# main.net
KiCad netlist of a schematic drawn in EAGLE
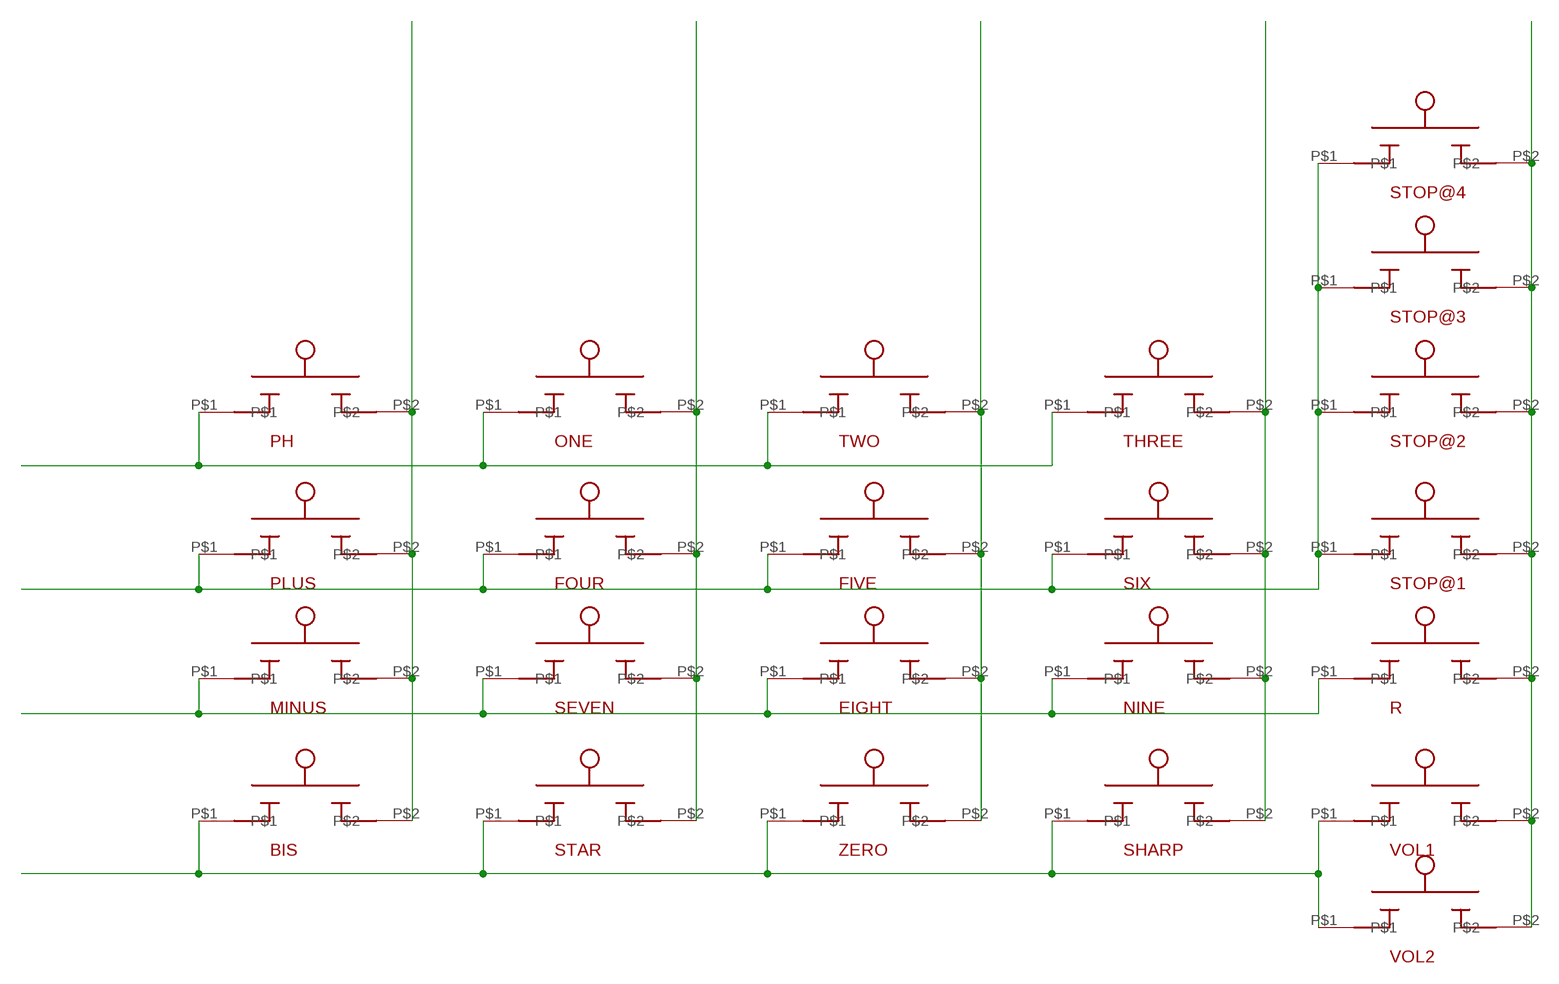
[diagram p0: schematic, sheet 1]

(export (version "E")
  (design (tool "Eeschema 10.0.6"))
  (components
    (comp (ref "BIS")
      (value "MEMBRANE_BUTTON")
      (footprint "eagle-import:MEMBRANE_BUTTON")
      (libsource (lib "eagle-import") (part "MEMBRANE_BUTTON"))
    )
    (comp (ref "EIGHT")
      (value "MEMBRANE_BUTTON")
      (footprint "eagle-import:MEMBRANE_BUTTON")
      (libsource (lib "eagle-import") (part "MEMBRANE_BUTTON"))
    )
    (comp (ref "FIVE")
      (value "MEMBRANE_BUTTON")
      (footprint "eagle-import:MEMBRANE_BUTTON")
      (libsource (lib "eagle-import") (part "MEMBRANE_BUTTON"))
    )
    (comp (ref "FOUR")
      (value "MEMBRANE_BUTTON")
      (footprint "eagle-import:MEMBRANE_BUTTON")
      (libsource (lib "eagle-import") (part "MEMBRANE_BUTTON"))
    )
    (comp (ref "MINUS")
      (value "MEMBRANE_BUTTON")
      (footprint "eagle-import:MEMBRANE_BUTTON")
      (libsource (lib "eagle-import") (part "MEMBRANE_BUTTON"))
    )
    (comp (ref "NINE")
      (value "MEMBRANE_BUTTON")
      (footprint "eagle-import:MEMBRANE_BUTTON")
      (libsource (lib "eagle-import") (part "MEMBRANE_BUTTON"))
    )
    (comp (ref "ONE")
      (value "MEMBRANE_BUTTON")
      (footprint "eagle-import:MEMBRANE_BUTTON")
      (libsource (lib "eagle-import") (part "MEMBRANE_BUTTON"))
    )
    (comp (ref "PH")
      (value "MEMBRANE_BUTTON")
      (footprint "eagle-import:MEMBRANE_BUTTON")
      (libsource (lib "eagle-import") (part "MEMBRANE_BUTTON"))
    )
    (comp (ref "PLUS")
      (value "MEMBRANE_BUTTON")
      (footprint "eagle-import:MEMBRANE_BUTTON")
      (libsource (lib "eagle-import") (part "MEMBRANE_BUTTON"))
    )
    (comp (ref "R")
      (value "MEMBRANE_BUTTON")
      (footprint "eagle-import:MEMBRANE_BUTTON")
      (libsource (lib "eagle-import") (part "MEMBRANE_BUTTON"))
    )
    (comp (ref "SEVEN")
      (value "MEMBRANE_BUTTON")
      (footprint "eagle-import:MEMBRANE_BUTTON")
      (libsource (lib "eagle-import") (part "MEMBRANE_BUTTON"))
    )
    (comp (ref "SHARP")
      (value "MEMBRANE_BUTTON")
      (footprint "eagle-import:MEMBRANE_BUTTON")
      (libsource (lib "eagle-import") (part "MEMBRANE_BUTTON"))
    )
    (comp (ref "SIX")
      (value "MEMBRANE_BUTTON")
      (footprint "eagle-import:MEMBRANE_BUTTON")
      (libsource (lib "eagle-import") (part "MEMBRANE_BUTTON"))
    )
    (comp (ref "STAR")
      (value "MEMBRANE_BUTTON")
      (footprint "eagle-import:MEMBRANE_BUTTON")
      (libsource (lib "eagle-import") (part "MEMBRANE_BUTTON"))
    )
    (comp (ref "STOP@1")
      (value "MEMBRANE_BUTTON")
      (footprint "eagle-import:MEMBRANE_BUTTON")
      (libsource (lib "eagle-import") (part "MEMBRANE_BUTTON"))
    )
    (comp (ref "STOP@2")
      (value "MEMBRANE_BUTTON")
      (footprint "eagle-import:MEMBRANE_BUTTON")
      (libsource (lib "eagle-import") (part "MEMBRANE_BUTTON"))
    )
    (comp (ref "STOP@3")
      (value "MEMBRANE_BUTTON")
      (footprint "eagle-import:MEMBRANE_BUTTON")
      (libsource (lib "eagle-import") (part "MEMBRANE_BUTTON"))
    )
    (comp (ref "STOP@4")
      (value "MEMBRANE_BUTTON")
      (footprint "eagle-import:MEMBRANE_BUTTON")
      (libsource (lib "eagle-import") (part "MEMBRANE_BUTTON"))
    )
    (comp (ref "THREE")
      (value "MEMBRANE_BUTTON")
      (footprint "eagle-import:MEMBRANE_BUTTON")
      (libsource (lib "eagle-import") (part "MEMBRANE_BUTTON"))
    )
    (comp (ref "TWO")
      (value "MEMBRANE_BUTTON")
      (footprint "eagle-import:MEMBRANE_BUTTON")
      (libsource (lib "eagle-import") (part "MEMBRANE_BUTTON"))
    )
    (comp (ref "VOL1")
      (value "MEMBRANE_BUTTON")
      (footprint "eagle-import:MEMBRANE_BUTTON")
      (libsource (lib "eagle-import") (part "MEMBRANE_BUTTON"))
    )
    (comp (ref "VOL2")
      (value "MEMBRANE_BUTTON")
      (footprint "eagle-import:MEMBRANE_BUTTON")
      (libsource (lib "eagle-import") (part "MEMBRANE_BUTTON"))
    )
    (comp (ref "ZERO")
      (value "MEMBRANE_BUTTON")
      (footprint "eagle-import:MEMBRANE_BUTTON")
      (libsource (lib "eagle-import") (part "MEMBRANE_BUTTON"))
    )
  )
  (nets
    (net (code "1") (name "Net-(BIS-PadP$1)") (class "Default")
      (node (ref "BIS") (pin "P$1") (pinfunction "P$1_P$1") (pintype "bidirectional"))
      (node (ref "SHARP") (pin "P$1") (pinfunction "P$1_P$1") (pintype "bidirectional"))
      (node (ref "STAR") (pin "P$1") (pinfunction "P$1_P$1") (pintype "bidirectional"))
      (node (ref "VOL1") (pin "P$1") (pinfunction "P$1_P$1") (pintype "bidirectional"))
      (node (ref "VOL2") (pin "P$1") (pinfunction "P$1_P$1") (pintype "bidirectional"))
      (node (ref "ZERO") (pin "P$1") (pinfunction "P$1_P$1") (pintype "bidirectional"))
    )
    (net (code "2") (name "Net-(BIS-PadP$2)") (class "Default")
      (node (ref "BIS") (pin "P$2") (pinfunction "P$2_P$2") (pintype "bidirectional"))
      (node (ref "MINUS") (pin "P$2") (pinfunction "P$2_P$2") (pintype "bidirectional"))
      (node (ref "PH") (pin "P$2") (pinfunction "P$2_P$2") (pintype "bidirectional"))
      (node (ref "PLUS") (pin "P$2") (pinfunction "P$2_P$2") (pintype "bidirectional"))
    )
    (net (code "3") (name "Net-(EIGHT-PadP$1)") (class "Default")
      (node (ref "EIGHT") (pin "P$1") (pinfunction "P$1_P$1") (pintype "bidirectional"))
      (node (ref "MINUS") (pin "P$1") (pinfunction "P$1_P$1") (pintype "bidirectional"))
      (node (ref "NINE") (pin "P$1") (pinfunction "P$1_P$1") (pintype "bidirectional"))
      (node (ref "R") (pin "P$1") (pinfunction "P$1_P$1") (pintype "bidirectional"))
      (node (ref "SEVEN") (pin "P$1") (pinfunction "P$1_P$1") (pintype "bidirectional"))
    )
    (net (code "4") (name "Net-(EIGHT-PadP$2)") (class "Default")
      (node (ref "EIGHT") (pin "P$2") (pinfunction "P$2_P$2") (pintype "bidirectional"))
      (node (ref "FIVE") (pin "P$2") (pinfunction "P$2_P$2") (pintype "bidirectional"))
      (node (ref "TWO") (pin "P$2") (pinfunction "P$2_P$2") (pintype "bidirectional"))
      (node (ref "ZERO") (pin "P$2") (pinfunction "P$2_P$2") (pintype "bidirectional"))
    )
    (net (code "5") (name "Net-(FIVE-PadP$1)") (class "Default")
      (node (ref "FIVE") (pin "P$1") (pinfunction "P$1_P$1") (pintype "bidirectional"))
      (node (ref "FOUR") (pin "P$1") (pinfunction "P$1_P$1") (pintype "bidirectional"))
      (node (ref "PLUS") (pin "P$1") (pinfunction "P$1_P$1") (pintype "bidirectional"))
      (node (ref "SIX") (pin "P$1") (pinfunction "P$1_P$1") (pintype "bidirectional"))
      (node (ref "STOP@1") (pin "P$1") (pinfunction "P$1_P$1") (pintype "bidirectional"))
      (node (ref "STOP@2") (pin "P$1") (pinfunction "P$1_P$1") (pintype "bidirectional"))
      (node (ref "STOP@3") (pin "P$1") (pinfunction "P$1_P$1") (pintype "bidirectional"))
      (node (ref "STOP@4") (pin "P$1") (pinfunction "P$1_P$1") (pintype "bidirectional"))
    )
    (net (code "6") (name "Net-(FOUR-PadP$2)") (class "Default")
      (node (ref "FOUR") (pin "P$2") (pinfunction "P$2_P$2") (pintype "bidirectional"))
      (node (ref "ONE") (pin "P$2") (pinfunction "P$2_P$2") (pintype "bidirectional"))
      (node (ref "SEVEN") (pin "P$2") (pinfunction "P$2_P$2") (pintype "bidirectional"))
      (node (ref "STAR") (pin "P$2") (pinfunction "P$2_P$2") (pintype "bidirectional"))
    )
    (net (code "7") (name "Net-(NINE-PadP$2)") (class "Default")
      (node (ref "NINE") (pin "P$2") (pinfunction "P$2_P$2") (pintype "bidirectional"))
      (node (ref "SHARP") (pin "P$2") (pinfunction "P$2_P$2") (pintype "bidirectional"))
      (node (ref "SIX") (pin "P$2") (pinfunction "P$2_P$2") (pintype "bidirectional"))
      (node (ref "THREE") (pin "P$2") (pinfunction "P$2_P$2") (pintype "bidirectional"))
    )
    (net (code "8") (name "Net-(ONE-PadP$1)") (class "Default")
      (node (ref "ONE") (pin "P$1") (pinfunction "P$1_P$1") (pintype "bidirectional"))
      (node (ref "PH") (pin "P$1") (pinfunction "P$1_P$1") (pintype "bidirectional"))
      (node (ref "THREE") (pin "P$1") (pinfunction "P$1_P$1") (pintype "bidirectional"))
      (node (ref "TWO") (pin "P$1") (pinfunction "P$1_P$1") (pintype "bidirectional"))
    )
    (net (code "9") (name "Net-(R-PadP$2)") (class "Default")
      (node (ref "R") (pin "P$2") (pinfunction "P$2_P$2") (pintype "bidirectional"))
      (node (ref "STOP@1") (pin "P$2") (pinfunction "P$2_P$2") (pintype "bidirectional"))
      (node (ref "STOP@2") (pin "P$2") (pinfunction "P$2_P$2") (pintype "bidirectional"))
      (node (ref "STOP@3") (pin "P$2") (pinfunction "P$2_P$2") (pintype "bidirectional"))
      (node (ref "STOP@4") (pin "P$2") (pinfunction "P$2_P$2") (pintype "bidirectional"))
      (node (ref "VOL1") (pin "P$2") (pinfunction "P$2_P$2") (pintype "bidirectional"))
      (node (ref "VOL2") (pin "P$2") (pinfunction "P$2_P$2") (pintype "bidirectional"))
    )
  )
)
